# DSO_CPLD.net
KiCad netlist of a schematic drawn in Altium Designer
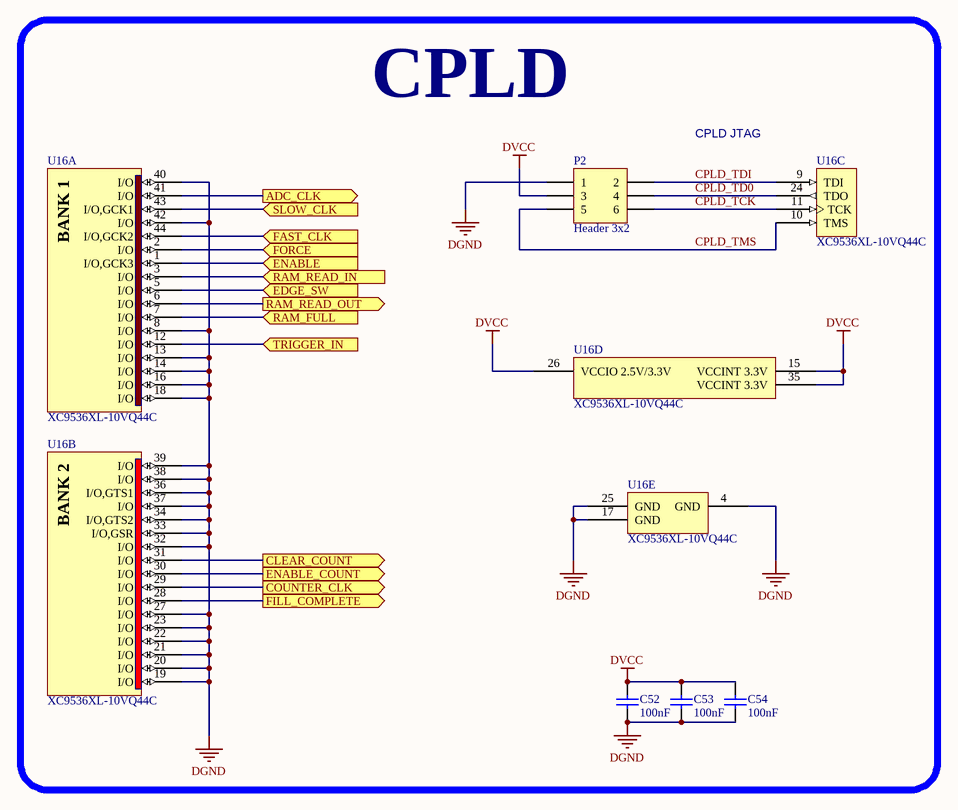
[diagram p0: DSO_CPLD.SchDoc]

(export (version "E")
  (design (tool "Eeschema 10.0.6"))
  (components
    (comp (ref "C52")
      (value "100nF")
      (footprint "0805C")
      (description "Capacitor")
      (fields (field (name "REVIEWED BY") "RM - 2018/08/05"))
      (libsource (lib "DSO") (part "C"))
    )
    (comp (ref "C53")
      (value "100nF")
      (footprint "0805C")
      (description "Capacitor")
      (fields (field (name "REVIEWED BY") "RM - 2018/08/05"))
      (libsource (lib "DSO") (part "C"))
    )
    (comp (ref "C54")
      (value "100nF")
      (footprint "0805C")
      (description "Capacitor")
      (fields (field (name "REVIEWED BY") "RM - 2018/08/05"))
      (libsource (lib "DSO") (part "C"))
    )
    (comp (ref "P2")
      (value "Header 3x2")
      (footprint "HDR3x2")
      (description "Header, 5-Pin")
      (fields (field (name "REVIEWED BY") "RM - 2018/08/05"))
      (libsource (lib "DSO") (part "Header 3x2"))
    )
    (comp (ref "U16")
      (value "XC9536XL-10VQ44C")
      (footprint "VQ44_L")
      (fields (field (name "REVIEWED BY") "RM - 2018/08/05"))
      (libsource (lib "DSO") (part "XC9536XL-10VQG44C"))
    )
  )
  (nets
    (net (code "1") (name "/ADC_CLK") (class "Default")
      (node (ref "U16") (pin "41") (pinfunction "I/O_41") (pintype "bidirectional"))
    )
    (net (code "2") (name "/CLEAR_COUNT") (class "Default")
      (node (ref "U16") (pin "31") (pinfunction "I/O_31") (pintype "bidirectional"))
    )
    (net (code "3") (name "/COUNTER_CLK") (class "Default")
      (node (ref "U16") (pin "29") (pinfunction "I/O_29") (pintype "bidirectional"))
    )
    (net (code "4") (name "/CPLD_TCK") (class "Default")
      (node (ref "P2") (pin "6") (pinfunction "6_6") (pintype "passive"))
      (node (ref "U16") (pin "11") (pinfunction "TCK_11") (pintype "input"))
    )
    (net (code "5") (name "/CPLD_TD0") (class "Default")
      (node (ref "P2") (pin "4") (pinfunction "4_4") (pintype "passive"))
      (node (ref "U16") (pin "24") (pinfunction "TDO_24") (pintype "output"))
    )
    (net (code "6") (name "/CPLD_TDI") (class "Default")
      (node (ref "P2") (pin "2") (pinfunction "2_2") (pintype "passive"))
      (node (ref "U16") (pin "9") (pinfunction "TDI_9") (pintype "input"))
    )
    (net (code "7") (name "/CPLD_TMS") (class "Default")
      (node (ref "P2") (pin "5") (pinfunction "5_5") (pintype "passive"))
      (node (ref "U16") (pin "10") (pinfunction "TMS_10") (pintype "input"))
    )
    (net (code "8") (name "/EDGE_SW") (class "Default")
      (node (ref "U16") (pin "5") (pinfunction "I/O_5") (pintype "bidirectional"))
    )
    (net (code "9") (name "/ENABLE") (class "Default")
      (node (ref "U16") (pin "1") (pinfunction "I/O,GCK3_1") (pintype "bidirectional"))
    )
    (net (code "10") (name "/ENABLE_COUNT") (class "Default")
      (node (ref "U16") (pin "30") (pinfunction "I/O_30") (pintype "bidirectional"))
    )
    (net (code "11") (name "/FAST_CLK") (class "Default")
      (node (ref "U16") (pin "44") (pinfunction "I/O,GCK2_44") (pintype "bidirectional"))
    )
    (net (code "12") (name "/FILL_COMPLETE") (class "Default")
      (node (ref "U16") (pin "28") (pinfunction "I/O_28") (pintype "bidirectional"))
    )
    (net (code "13") (name "/FORCE") (class "Default")
      (node (ref "U16") (pin "2") (pinfunction "I/O_2") (pintype "bidirectional"))
    )
    (net (code "14") (name "/RAM_FULL") (class "Default")
      (node (ref "U16") (pin "7") (pinfunction "I/O_7") (pintype "bidirectional"))
    )
    (net (code "15") (name "/RAM_READ_IN") (class "Default")
      (node (ref "U16") (pin "3") (pinfunction "I/O_3") (pintype "bidirectional"))
    )
    (net (code "16") (name "/RAM_READ_OUT") (class "Default")
      (node (ref "U16") (pin "6") (pinfunction "I/O_6") (pintype "bidirectional"))
    )
    (net (code "17") (name "/SLOW_CLK") (class "Default")
      (node (ref "U16") (pin "43") (pinfunction "I/O,GCK1_43") (pintype "bidirectional"))
    )
    (net (code "18") (name "/TRIGGER_IN") (class "Default")
      (node (ref "U16") (pin "12") (pinfunction "I/O_12") (pintype "bidirectional"))
    )
    (net (code "19") (name "DGND") (class "Default")
      (node (ref "C52") (pin "2") (pinfunction "2_2") (pintype "passive"))
      (node (ref "C53") (pin "2") (pinfunction "2_2") (pintype "passive"))
      (node (ref "C54") (pin "2") (pinfunction "2_2") (pintype "passive"))
      (node (ref "P2") (pin "1") (pinfunction "1_1") (pintype "passive"))
      (node (ref "U16") (pin "13") (pinfunction "I/O_13") (pintype "bidirectional"))
      (node (ref "U16") (pin "14") (pinfunction "I/O_14") (pintype "bidirectional"))
      (node (ref "U16") (pin "16") (pinfunction "I/O_16") (pintype "bidirectional"))
      (node (ref "U16") (pin "17") (pinfunction "GND_17") (pintype "power_in"))
      (node (ref "U16") (pin "18") (pinfunction "I/O_18") (pintype "bidirectional"))
      (node (ref "U16") (pin "19") (pinfunction "I/O_19") (pintype "bidirectional"))
      (node (ref "U16") (pin "20") (pinfunction "I/O_20") (pintype "bidirectional"))
      (node (ref "U16") (pin "21") (pinfunction "I/O_21") (pintype "bidirectional"))
      (node (ref "U16") (pin "22") (pinfunction "I/O_22") (pintype "bidirectional"))
      (node (ref "U16") (pin "23") (pinfunction "I/O_23") (pintype "bidirectional"))
      (node (ref "U16") (pin "25") (pinfunction "GND_25") (pintype "power_in"))
      (node (ref "U16") (pin "27") (pinfunction "I/O_27") (pintype "bidirectional"))
      (node (ref "U16") (pin "32") (pinfunction "I/O_32") (pintype "bidirectional"))
      (node (ref "U16") (pin "33") (pinfunction "I/O,GSR_33") (pintype "bidirectional"))
      (node (ref "U16") (pin "34") (pinfunction "I/O,GTS2_34") (pintype "bidirectional"))
      (node (ref "U16") (pin "36") (pinfunction "I/O,GTS1_36") (pintype "bidirectional"))
      (node (ref "U16") (pin "37") (pinfunction "I/O_37") (pintype "bidirectional"))
      (node (ref "U16") (pin "38") (pinfunction "I/O_38") (pintype "bidirectional"))
      (node (ref "U16") (pin "39") (pinfunction "I/O_39") (pintype "bidirectional"))
      (node (ref "U16") (pin "4") (pinfunction "GND_4") (pintype "power_in"))
      (node (ref "U16") (pin "40") (pinfunction "I/O_40") (pintype "bidirectional"))
      (node (ref "U16") (pin "42") (pinfunction "I/O_42") (pintype "bidirectional"))
      (node (ref "U16") (pin "8") (pinfunction "I/O_8") (pintype "bidirectional"))
    )
    (net (code "20") (name "DVCC") (class "Default")
      (node (ref "C52") (pin "1") (pinfunction "1_1") (pintype "passive"))
      (node (ref "C53") (pin "1") (pinfunction "1_1") (pintype "passive"))
      (node (ref "C54") (pin "1") (pinfunction "1_1") (pintype "passive"))
      (node (ref "P2") (pin "3") (pinfunction "3_3") (pintype "passive"))
      (node (ref "U16") (pin "15") (pinfunction "VCCINT_3.3V_15") (pintype "power_in"))
      (node (ref "U16") (pin "26") (pinfunction "VCCIO_2.5V/3.3V_26") (pintype "power_in"))
      (node (ref "U16") (pin "35") (pinfunction "VCCINT_3.3V_35") (pintype "power_in"))
    )
  )
)
